# 9led-breakout.net
KiCad netlist of a schematic drawn in EAGLE
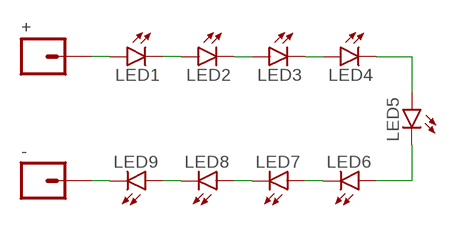
[diagram p0: schematic, sheet 1]

(export (version "E")
  (design (tool "Eeschema 10.0.6"))
  (components
    (comp (ref "+")
      (value "M01PTH-KIT")
      (footprint "eagle-import:1X01-KIT")
      (libsource (lib "eagle-import") (part "M01PTH-KIT"))
    )
    (comp (ref "-")
      (value "M01NOSILK-KIT")
      (footprint "eagle-import:1X01NS-KIT")
      (libsource (lib "eagle-import") (part "M01NOSILK-KIT"))
    )
    (comp (ref "LED1")
      (value "LED5MM")
      (footprint "eagle-import:LED5MM")
      (libsource (lib "eagle-import") (part "LED5MM"))
    )
    (comp (ref "LED2")
      (value "LED5MM")
      (footprint "eagle-import:LED5MM")
      (libsource (lib "eagle-import") (part "LED5MM"))
    )
    (comp (ref "LED3")
      (value "LED5MM")
      (footprint "eagle-import:LED5MM")
      (libsource (lib "eagle-import") (part "LED5MM"))
    )
    (comp (ref "LED4")
      (value "LED5MM")
      (footprint "eagle-import:LED5MM")
      (libsource (lib "eagle-import") (part "LED5MM"))
    )
    (comp (ref "LED5")
      (value "LED5MM")
      (footprint "eagle-import:LED5MM")
      (libsource (lib "eagle-import") (part "LED5MM"))
    )
    (comp (ref "LED6")
      (value "LED5MM")
      (footprint "eagle-import:LED5MM")
      (libsource (lib "eagle-import") (part "LED5MM"))
    )
    (comp (ref "LED7")
      (value "LED5MM")
      (footprint "eagle-import:LED5MM")
      (libsource (lib "eagle-import") (part "LED5MM"))
    )
    (comp (ref "LED8")
      (value "LED5MM")
      (footprint "eagle-import:LED5MM")
      (libsource (lib "eagle-import") (part "LED5MM"))
    )
    (comp (ref "LED9")
      (value "LED5MM")
      (footprint "eagle-import:LED5MM")
      (libsource (lib "eagle-import") (part "LED5MM"))
    )
  )
  (nets
    (net (code "1") (name "Net-(+-Pad1)") (class "Default")
      (node (ref "+") (pin "1") (pinfunction "1_1") (pintype "passive"))
      (node (ref "LED1") (pin "A") (pinfunction "A_A") (pintype "passive"))
    )
    (net (code "2") (name "Net-(LED1-C)") (class "Default")
      (node (ref "LED1") (pin "K") (pinfunction "C_K") (pintype "passive"))
      (node (ref "LED2") (pin "A") (pinfunction "A_A") (pintype "passive"))
    )
    (net (code "3") (name "Net-(LED2-C)") (class "Default")
      (node (ref "LED2") (pin "K") (pinfunction "C_K") (pintype "passive"))
      (node (ref "LED3") (pin "A") (pinfunction "A_A") (pintype "passive"))
    )
    (net (code "4") (name "Net-(LED3-C)") (class "Default")
      (node (ref "LED3") (pin "K") (pinfunction "C_K") (pintype "passive"))
      (node (ref "LED4") (pin "A") (pinfunction "A_A") (pintype "passive"))
    )
    (net (code "5") (name "Net-(LED4-C)") (class "Default")
      (node (ref "LED4") (pin "K") (pinfunction "C_K") (pintype "passive"))
      (node (ref "LED5") (pin "A") (pinfunction "A_A") (pintype "passive"))
    )
    (net (code "6") (name "Net-(LED5-C)") (class "Default")
      (node (ref "LED5") (pin "K") (pinfunction "C_K") (pintype "passive"))
      (node (ref "LED6") (pin "A") (pinfunction "A_A") (pintype "passive"))
    )
    (net (code "7") (name "Net-(LED6-C)") (class "Default")
      (node (ref "LED6") (pin "K") (pinfunction "C_K") (pintype "passive"))
      (node (ref "LED7") (pin "A") (pinfunction "A_A") (pintype "passive"))
    )
    (net (code "8") (name "Net-(LED7-C)") (class "Default")
      (node (ref "LED7") (pin "K") (pinfunction "C_K") (pintype "passive"))
      (node (ref "LED8") (pin "A") (pinfunction "A_A") (pintype "passive"))
    )
    (net (code "9") (name "Net-(LED8-C)") (class "Default")
      (node (ref "LED8") (pin "K") (pinfunction "C_K") (pintype "passive"))
      (node (ref "LED9") (pin "A") (pinfunction "A_A") (pintype "passive"))
    )
    (net (code "10") (name "Net-(LED9-C)") (class "Default")
      (node (ref "-") (pin "1") (pinfunction "1_1") (pintype "passive"))
      (node (ref "LED9") (pin "K") (pinfunction "C_K") (pintype "passive"))
    )
  )
)
